# motor_servo_control.net
KiCad netlist of a schematic drawn in EAGLE
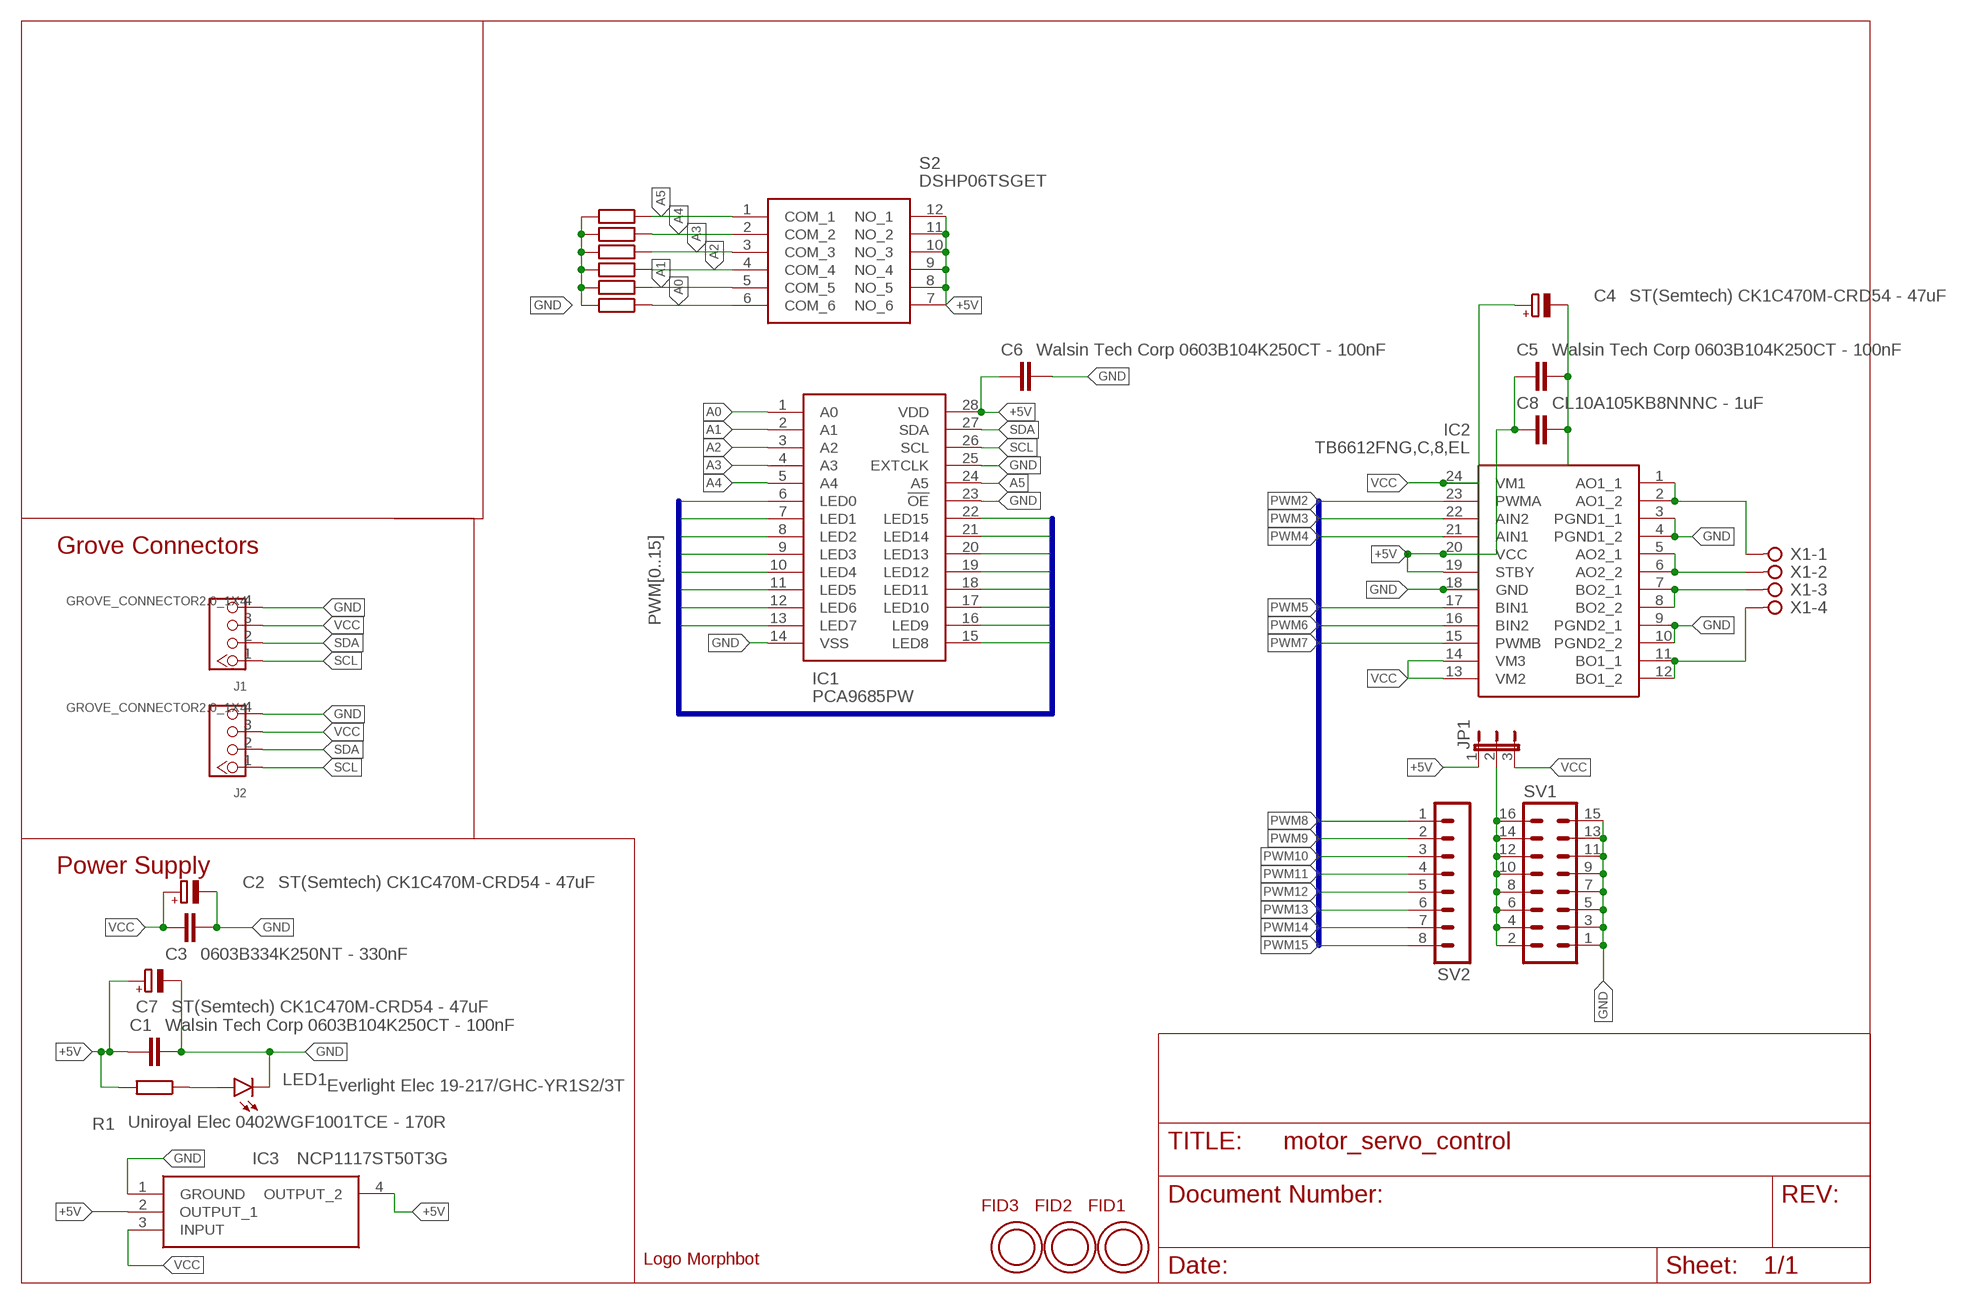
[diagram p0: schematic, sheet 1]

(export (version "E")
  (design (tool "Eeschema 10.0.6"))
  (components
    (comp (ref "C1")
      (value "Walsin Tech Corp 0603B104K250CT - 100nF")
      (footprint "eagle-import:C0603")
      (libsource (lib "eagle-import") (part "C-EUC0603"))
    )
    (comp (ref "C2")
      (value "ST(Semtech) CK1C470M-CRD54 - 47uF")
      (footprint "eagle-import:PANASONIC_C")
      (libsource (lib "eagle-import") (part "CPOL-EUC"))
    )
    (comp (ref "C3")
      (value "0603B334K250NT - 330nF")
      (footprint "eagle-import:C0603")
      (libsource (lib "eagle-import") (part "C-EUC0603"))
    )
    (comp (ref "C4")
      (value "ST(Semtech) CK1C470M-CRD54 - 47uF")
      (footprint "eagle-import:PANASONIC_C")
      (libsource (lib "eagle-import") (part "CPOL-EUC"))
    )
    (comp (ref "C5")
      (value "Walsin Tech Corp 0603B104K250CT - 100nF")
      (footprint "eagle-import:C0603")
      (libsource (lib "eagle-import") (part "C-EUC0603"))
    )
    (comp (ref "C6")
      (value "Walsin Tech Corp 0603B104K250CT - 100nF")
      (footprint "eagle-import:C0603")
      (libsource (lib "eagle-import") (part "C-EUC0603"))
    )
    (comp (ref "C7")
      (value "ST(Semtech) CK1C470M-CRD54 - 47uF")
      (footprint "eagle-import:PANASONIC_C")
      (libsource (lib "eagle-import") (part "CPOL-EUC"))
    )
    (comp (ref "C8")
      (value "CL10A105KB8NNNC - 1uF")
      (footprint "eagle-import:C0603")
      (libsource (lib "eagle-import") (part "C-EUC0603"))
    )
    (comp (ref "FID1")
      (value "OPEN-PNP-FIDUCIAL")
      (footprint "eagle-import:OPEN-PNP-FIDUCIAL")
      (libsource (lib "eagle-import") (part "OPEN-PNP-FIDUCIAL"))
    )
    (comp (ref "FID2")
      (value "OPEN-PNP-FIDUCIAL")
      (footprint "eagle-import:OPEN-PNP-FIDUCIAL")
      (libsource (lib "eagle-import") (part "OPEN-PNP-FIDUCIAL"))
    )
    (comp (ref "FID3")
      (value "OPEN-PNP-FIDUCIAL")
      (footprint "eagle-import:OPEN-PNP-FIDUCIAL")
      (libsource (lib "eagle-import") (part "OPEN-PNP-FIDUCIAL"))
    )
    (comp (ref "IC1")
      (value "PCA9685PW")
      (footprint "eagle-import:SOP65P640X110-28N")
      (libsource (lib "eagle-import") (part "PCA9685PW"))
    )
    (comp (ref "IC2")
      (value "TB6612FNG,C,8,EL")
      (footprint "eagle-import:SOP65P760X160-24N")
      (fields (field (name "MOUSER_PART_NUMBER") "757-TB6612FNGC8EL"))
      (libsource (lib "eagle-import") (part "TB6612FNG,C,8,EL"))
    )
    (comp (ref "IC3")
      (value "NCP1117ST50T3G")
      (footprint "eagle-import:SOT230P700X180-4N")
      (fields (field (name "MOUSER_PART_NUMBER") "863-NCP1117ST50T3G"))
      (libsource (lib "eagle-import") (part "NCP1117ST50T3G"))
    )
    (comp (ref "J1")
      (value "GROVE_CONNECTOR2.0_1X4")
      (footprint "eagle-import:2.0_1X4_STRAIGHT")
      (libsource (lib "eagle-import") (part "GROVE_CONNECTOR2.0_1X4"))
    )
    (comp (ref "J2")
      (value "GROVE_CONNECTOR2.0_1X4")
      (footprint "eagle-import:2.0_1X4_STRAIGHT")
      (libsource (lib "eagle-import") (part "GROVE_CONNECTOR2.0_1X4"))
    )
    (comp (ref "JP1")
      (value "JP2E")
      (footprint "eagle-import:JP2")
      (libsource (lib "eagle-import") (part "JP2E"))
    )
    (comp (ref "LED1")
      (value "Everlight Elec 19-217/GHC-YR1S2/3T")
      (footprint "eagle-import:CHIPLED_0603")
      (libsource (lib "eagle-import") (part "LEDCHIPLED_0603"))
    )
    (comp (ref "R1")
      (value "Uniroyal Elec 0402WGF1001TCE - 170R")
      (footprint "eagle-import:R0402")
      (libsource (lib "eagle-import") (part "R-EU_R0402"))
    )
    (comp (ref "R2")
      (value "0402WGF1002TCE - 10k")
      (footprint "eagle-import:R0402")
      (libsource (lib "eagle-import") (part "R-EU_R0402"))
    )
    (comp (ref "R3")
      (value "0402WGF1002TCE - 10k")
      (footprint "eagle-import:R0402")
      (libsource (lib "eagle-import") (part "R-EU_R0402"))
    )
    (comp (ref "R4")
      (value "0402WGF1002TCE - 10k")
      (footprint "eagle-import:R0402")
      (libsource (lib "eagle-import") (part "R-EU_R0402"))
    )
    (comp (ref "R5")
      (value "0402WGF1002TCE - 10k")
      (footprint "eagle-import:R0402")
      (libsource (lib "eagle-import") (part "R-EU_R0402"))
    )
    (comp (ref "R6")
      (value "0402WGF1002TCE - 10k")
      (footprint "eagle-import:R0402")
      (libsource (lib "eagle-import") (part "R-EU_R0402"))
    )
    (comp (ref "R7")
      (value "0402WGF1002TCE - 10k")
      (footprint "eagle-import:R0402")
      (libsource (lib "eagle-import") (part "R-EU_R0402"))
    )
    (comp (ref "S2")
      (value "DSHP06TSGET")
      (footprint "eagle-import:DSHP06TSGET")
      (libsource (lib "eagle-import") (part "DSHP06TSGET"))
    )
    (comp (ref "SV1")
      (value "MA08-2")
      (footprint "eagle-import:MA08-2")
      (libsource (lib "eagle-import") (part "MA08-2"))
    )
    (comp (ref "SV2")
      (value "MA08-1")
      (footprint "eagle-import:MA08-1")
      (libsource (lib "eagle-import") (part "MA08-1"))
    )
    (comp (ref "U$1")
      (value "LOGO_MORPHBOT5MM")
      (footprint "eagle-import:LOGO_MORPHBOT")
      (libsource (lib "eagle-import") (part "LOGO_MORPHBOT5MM"))
    )
    (comp (ref "X1")
      (value "W237-04P")
      (footprint "eagle-import:W237-4P")
      (libsource (lib "eagle-import") (part "W237-04P"))
    )
  )
  (nets
    (net (code "3") (name "+5V") (class "Default")
      (node (ref "C1") (pin "1") (pinfunction "1_1") (pintype "passive"))
      (node (ref "C5") (pin "1") (pinfunction "1_1") (pintype "passive"))
      (node (ref "C6") (pin "1") (pinfunction "1_1") (pintype "passive"))
      (node (ref "C7") (pin "+") (pinfunction "+_+") (pintype "passive"))
      (node (ref "C8") (pin "1") (pinfunction "1_1") (pintype "passive"))
      (node (ref "IC1") (pin "28") (pinfunction "VDD_28") (pintype "bidirectional"))
      (node (ref "IC2") (pin "19") (pinfunction "STBY_19") (pintype "bidirectional"))
      (node (ref "IC2") (pin "20") (pinfunction "VCC_20") (pintype "bidirectional"))
      (node (ref "IC3") (pin "2") (pinfunction "OUTPUT_1_2") (pintype "bidirectional"))
      (node (ref "IC3") (pin "4") (pinfunction "OUTPUT_2_4") (pintype "bidirectional"))
      (node (ref "JP1") (pin "1") (pinfunction "1_1") (pintype "passive"))
      (node (ref "R1") (pin "2") (pinfunction "2_2") (pintype "passive"))
      (node (ref "S2") (pin "10") (pinfunction "NO_3_10") (pintype "bidirectional"))
      (node (ref "S2") (pin "11") (pinfunction "NO_2_11") (pintype "bidirectional"))
      (node (ref "S2") (pin "12") (pinfunction "NO_1_12") (pintype "bidirectional"))
      (node (ref "S2") (pin "7") (pinfunction "NO_6_7") (pintype "bidirectional"))
      (node (ref "S2") (pin "8") (pinfunction "NO_5_8") (pintype "bidirectional"))
      (node (ref "S2") (pin "9") (pinfunction "NO_4_9") (pintype "bidirectional"))
    )
    (net (code "5") (name "A0") (class "Default")
      (node (ref "IC1") (pin "1") (pinfunction "A0_1") (pintype "bidirectional"))
      (node (ref "R7") (pin "1") (pinfunction "1_1") (pintype "passive"))
      (node (ref "S2") (pin "6") (pinfunction "COM_6_6") (pintype "bidirectional"))
    )
    (net (code "6") (name "A1") (class "Default")
      (node (ref "IC1") (pin "2") (pinfunction "A1_2") (pintype "bidirectional"))
      (node (ref "R6") (pin "1") (pinfunction "1_1") (pintype "passive"))
      (node (ref "S2") (pin "5") (pinfunction "COM_5_5") (pintype "bidirectional"))
    )
    (net (code "7") (name "A2") (class "Default")
      (node (ref "IC1") (pin "3") (pinfunction "A2_3") (pintype "bidirectional"))
      (node (ref "R5") (pin "1") (pinfunction "1_1") (pintype "passive"))
      (node (ref "S2") (pin "4") (pinfunction "COM_4_4") (pintype "bidirectional"))
    )
    (net (code "8") (name "A3") (class "Default")
      (node (ref "IC1") (pin "4") (pinfunction "A3_4") (pintype "bidirectional"))
      (node (ref "R4") (pin "1") (pinfunction "1_1") (pintype "passive"))
      (node (ref "S2") (pin "3") (pinfunction "COM_3_3") (pintype "bidirectional"))
    )
    (net (code "9") (name "A4") (class "Default")
      (node (ref "IC1") (pin "5") (pinfunction "A4_5") (pintype "bidirectional"))
      (node (ref "R3") (pin "1") (pinfunction "1_1") (pintype "passive"))
      (node (ref "S2") (pin "2") (pinfunction "COM_2_2") (pintype "bidirectional"))
    )
    (net (code "10") (name "A5") (class "Default")
      (node (ref "IC1") (pin "24") (pinfunction "A5_24") (pintype "bidirectional"))
      (node (ref "R2") (pin "1") (pinfunction "1_1") (pintype "passive"))
      (node (ref "S2") (pin "1") (pinfunction "COM_1_1") (pintype "bidirectional"))
    )
    (net (code "11") (name "GND") (class "Default")
      (node (ref "C1") (pin "2") (pinfunction "2_2") (pintype "passive"))
      (node (ref "C2") (pin "-") (pinfunction "-_-") (pintype "passive"))
      (node (ref "C3") (pin "1") (pinfunction "1_1") (pintype "passive"))
      (node (ref "C4") (pin "-") (pinfunction "-_-") (pintype "passive"))
      (node (ref "C5") (pin "2") (pinfunction "2_2") (pintype "passive"))
      (node (ref "C6") (pin "2") (pinfunction "2_2") (pintype "passive"))
      (node (ref "C7") (pin "-") (pinfunction "-_-") (pintype "passive"))
      (node (ref "C8") (pin "2") (pinfunction "2_2") (pintype "passive"))
      (node (ref "IC1") (pin "14") (pinfunction "VSS_14") (pintype "bidirectional"))
      (node (ref "IC1") (pin "23") (pinfunction "~{OE}_23") (pintype "bidirectional"))
      (node (ref "IC1") (pin "25") (pinfunction "EXTCLK_25") (pintype "bidirectional"))
      (node (ref "IC2") (pin "10") (pinfunction "PGND2_2_10") (pintype "bidirectional"))
      (node (ref "IC2") (pin "18") (pinfunction "GND_18") (pintype "bidirectional"))
      (node (ref "IC2") (pin "3") (pinfunction "PGND1_1_3") (pintype "bidirectional"))
      (node (ref "IC2") (pin "4") (pinfunction "PGND1_2_4") (pintype "bidirectional"))
      (node (ref "IC2") (pin "9") (pinfunction "PGND2_1_9") (pintype "bidirectional"))
      (node (ref "IC3") (pin "1") (pinfunction "GROUND_1") (pintype "bidirectional"))
      (node (ref "J1") (pin "4") (pinfunction "4_4") (pintype "bidirectional"))
      (node (ref "J2") (pin "4") (pinfunction "4_4") (pintype "bidirectional"))
      (node (ref "LED1") (pin "C") (pinfunction "C_C") (pintype "passive"))
      (node (ref "R2") (pin "2") (pinfunction "2_2") (pintype "passive"))
      (node (ref "R3") (pin "2") (pinfunction "2_2") (pintype "passive"))
      (node (ref "R4") (pin "2") (pinfunction "2_2") (pintype "passive"))
      (node (ref "R5") (pin "2") (pinfunction "2_2") (pintype "passive"))
      (node (ref "R6") (pin "2") (pinfunction "2_2") (pintype "passive"))
      (node (ref "R7") (pin "2") (pinfunction "2_2") (pintype "passive"))
      (node (ref "SV1") (pin "1") (pinfunction "1_1") (pintype "passive"))
      (node (ref "SV1") (pin "11") (pinfunction "11_11") (pintype "passive"))
      (node (ref "SV1") (pin "13") (pinfunction "13_13") (pintype "passive"))
      (node (ref "SV1") (pin "15") (pinfunction "15_15") (pintype "passive"))
      (node (ref "SV1") (pin "3") (pinfunction "3_3") (pintype "passive"))
      (node (ref "SV1") (pin "5") (pinfunction "5_5") (pintype "passive"))
      (node (ref "SV1") (pin "7") (pinfunction "7_7") (pintype "passive"))
      (node (ref "SV1") (pin "9") (pinfunction "9_9") (pintype "passive"))
    )
    (net (code "12") (name "Net-(IC2-AO1_1)") (class "Default")
      (node (ref "IC2") (pin "1") (pinfunction "AO1_1_1") (pintype "bidirectional"))
      (node (ref "IC2") (pin "2") (pinfunction "AO1_2_2") (pintype "bidirectional"))
      (node (ref "X1") (pin "1") (pinfunction "KL_1") (pintype "passive"))
    )
    (net (code "13") (name "Net-(IC2-AO2_1)") (class "Default")
      (node (ref "IC2") (pin "5") (pinfunction "AO2_1_5") (pintype "bidirectional"))
      (node (ref "IC2") (pin "6") (pinfunction "AO2_2_6") (pintype "bidirectional"))
      (node (ref "X1") (pin "2") (pinfunction "KL_2") (pintype "passive"))
    )
    (net (code "14") (name "Net-(IC2-BO1_1)") (class "Default")
      (node (ref "IC2") (pin "11") (pinfunction "BO1_1_11") (pintype "bidirectional"))
      (node (ref "IC2") (pin "12") (pinfunction "BO1_2_12") (pintype "bidirectional"))
      (node (ref "X1") (pin "4") (pinfunction "KL_4") (pintype "passive"))
    )
    (net (code "15") (name "Net-(IC2-BO2_1)") (class "Default")
      (node (ref "IC2") (pin "7") (pinfunction "BO2_1_7") (pintype "bidirectional"))
      (node (ref "IC2") (pin "8") (pinfunction "BO2_2_8") (pintype "bidirectional"))
      (node (ref "X1") (pin "3") (pinfunction "KL_3") (pintype "passive"))
    )
    (net (code "16") (name "Net-(JP1-Pad2)") (class "Default")
      (node (ref "JP1") (pin "2") (pinfunction "2_2") (pintype "passive"))
      (node (ref "SV1") (pin "10") (pinfunction "10_10") (pintype "passive"))
      (node (ref "SV1") (pin "12") (pinfunction "12_12") (pintype "passive"))
      (node (ref "SV1") (pin "14") (pinfunction "14_14") (pintype "passive"))
      (node (ref "SV1") (pin "16") (pinfunction "16_16") (pintype "passive"))
      (node (ref "SV1") (pin "2") (pinfunction "2_2") (pintype "passive"))
      (node (ref "SV1") (pin "4") (pinfunction "4_4") (pintype "passive"))
      (node (ref "SV1") (pin "6") (pinfunction "6_6") (pintype "passive"))
      (node (ref "SV1") (pin "8") (pinfunction "8_8") (pintype "passive"))
    )
    (net (code "17") (name "Net-(LED1-PadA)") (class "Default")
      (node (ref "LED1") (pin "A") (pinfunction "A_A") (pintype "passive"))
      (node (ref "R1") (pin "1") (pinfunction "1_1") (pintype "passive"))
    )
    (net (code "18") (name "PWM2") (class "Default")
      (node (ref "IC1") (pin "8") (pinfunction "LED2_8") (pintype "bidirectional"))
      (node (ref "IC2") (pin "23") (pinfunction "PWMA_23") (pintype "bidirectional"))
    )
    (net (code "19") (name "PWM3") (class "Default")
      (node (ref "IC1") (pin "9") (pinfunction "LED3_9") (pintype "bidirectional"))
      (node (ref "IC2") (pin "22") (pinfunction "AIN2_22") (pintype "bidirectional"))
    )
    (net (code "20") (name "PWM4") (class "Default")
      (node (ref "IC1") (pin "10") (pinfunction "LED4_10") (pintype "bidirectional"))
      (node (ref "IC2") (pin "21") (pinfunction "AIN1_21") (pintype "bidirectional"))
    )
    (net (code "21") (name "PWM5") (class "Default")
      (node (ref "IC1") (pin "11") (pinfunction "LED5_11") (pintype "bidirectional"))
      (node (ref "IC2") (pin "17") (pinfunction "BIN1_17") (pintype "bidirectional"))
    )
    (net (code "22") (name "PWM6") (class "Default")
      (node (ref "IC1") (pin "12") (pinfunction "LED6_12") (pintype "bidirectional"))
      (node (ref "IC2") (pin "16") (pinfunction "BIN2_16") (pintype "bidirectional"))
    )
    (net (code "23") (name "PWM7") (class "Default")
      (node (ref "IC1") (pin "13") (pinfunction "LED7_13") (pintype "bidirectional"))
      (node (ref "IC2") (pin "15") (pinfunction "PWMB_15") (pintype "bidirectional"))
    )
    (net (code "24") (name "PWM8") (class "Default")
      (node (ref "IC1") (pin "15") (pinfunction "LED8_15") (pintype "bidirectional"))
      (node (ref "SV2") (pin "1") (pinfunction "1_1") (pintype "passive"))
    )
    (net (code "25") (name "PWM9") (class "Default")
      (node (ref "IC1") (pin "16") (pinfunction "LED9_16") (pintype "bidirectional"))
      (node (ref "SV2") (pin "2") (pinfunction "2_2") (pintype "passive"))
    )
    (net (code "26") (name "PWM10") (class "Default")
      (node (ref "IC1") (pin "17") (pinfunction "LED10_17") (pintype "bidirectional"))
      (node (ref "SV2") (pin "3") (pinfunction "3_3") (pintype "passive"))
    )
    (net (code "27") (name "PWM11") (class "Default")
      (node (ref "IC1") (pin "18") (pinfunction "LED11_18") (pintype "bidirectional"))
      (node (ref "SV2") (pin "4") (pinfunction "4_4") (pintype "passive"))
    )
    (net (code "28") (name "PWM12") (class "Default")
      (node (ref "IC1") (pin "19") (pinfunction "LED12_19") (pintype "bidirectional"))
      (node (ref "SV2") (pin "5") (pinfunction "5_5") (pintype "passive"))
    )
    (net (code "29") (name "PWM13") (class "Default")
      (node (ref "IC1") (pin "20") (pinfunction "LED13_20") (pintype "bidirectional"))
      (node (ref "SV2") (pin "6") (pinfunction "6_6") (pintype "passive"))
    )
    (net (code "30") (name "PWM14") (class "Default")
      (node (ref "IC1") (pin "21") (pinfunction "LED14_21") (pintype "bidirectional"))
      (node (ref "SV2") (pin "7") (pinfunction "7_7") (pintype "passive"))
    )
    (net (code "31") (name "PWM15") (class "Default")
      (node (ref "IC1") (pin "22") (pinfunction "LED15_22") (pintype "bidirectional"))
      (node (ref "SV2") (pin "8") (pinfunction "8_8") (pintype "passive"))
    )
    (net (code "32") (name "SCL") (class "Default")
      (node (ref "IC1") (pin "26") (pinfunction "SCL_26") (pintype "bidirectional"))
      (node (ref "J1") (pin "1") (pinfunction "1_1") (pintype "bidirectional"))
      (node (ref "J2") (pin "1") (pinfunction "1_1") (pintype "bidirectional"))
    )
    (net (code "33") (name "SDA") (class "Default")
      (node (ref "IC1") (pin "27") (pinfunction "SDA_27") (pintype "bidirectional"))
      (node (ref "J1") (pin "2") (pinfunction "2_2") (pintype "bidirectional"))
      (node (ref "J2") (pin "2") (pinfunction "2_2") (pintype "bidirectional"))
    )
    (net (code "34") (name "VCC") (class "Default")
      (node (ref "C2") (pin "+") (pinfunction "+_+") (pintype "passive"))
      (node (ref "C3") (pin "2") (pinfunction "2_2") (pintype "passive"))
      (node (ref "C4") (pin "+") (pinfunction "+_+") (pintype "passive"))
      (node (ref "IC2") (pin "13") (pinfunction "VM2_13") (pintype "bidirectional"))
      (node (ref "IC2") (pin "14") (pinfunction "VM3_14") (pintype "bidirectional"))
      (node (ref "IC2") (pin "24") (pinfunction "VM1_24") (pintype "bidirectional"))
      (node (ref "IC3") (pin "3") (pinfunction "INPUT_3") (pintype "bidirectional"))
      (node (ref "J1") (pin "3") (pinfunction "3_3") (pintype "bidirectional"))
      (node (ref "J2") (pin "3") (pinfunction "3_3") (pintype "bidirectional"))
      (node (ref "JP1") (pin "3") (pinfunction "3_3") (pintype "passive"))
    )
    (net (code "35") (name "unconnected-(IC1-LED0-Pad6)") (class "Default")
      (node (ref "IC1") (pin "6") (pinfunction "LED0_6") (pintype "bidirectional"))
    )
    (net (code "36") (name "unconnected-(IC1-LED1-Pad7)") (class "Default")
      (node (ref "IC1") (pin "7") (pinfunction "LED1_7") (pintype "bidirectional"))
    )
  )
)
